# modulo_promini.net
KiCad netlist of a schematic drawn in EAGLE
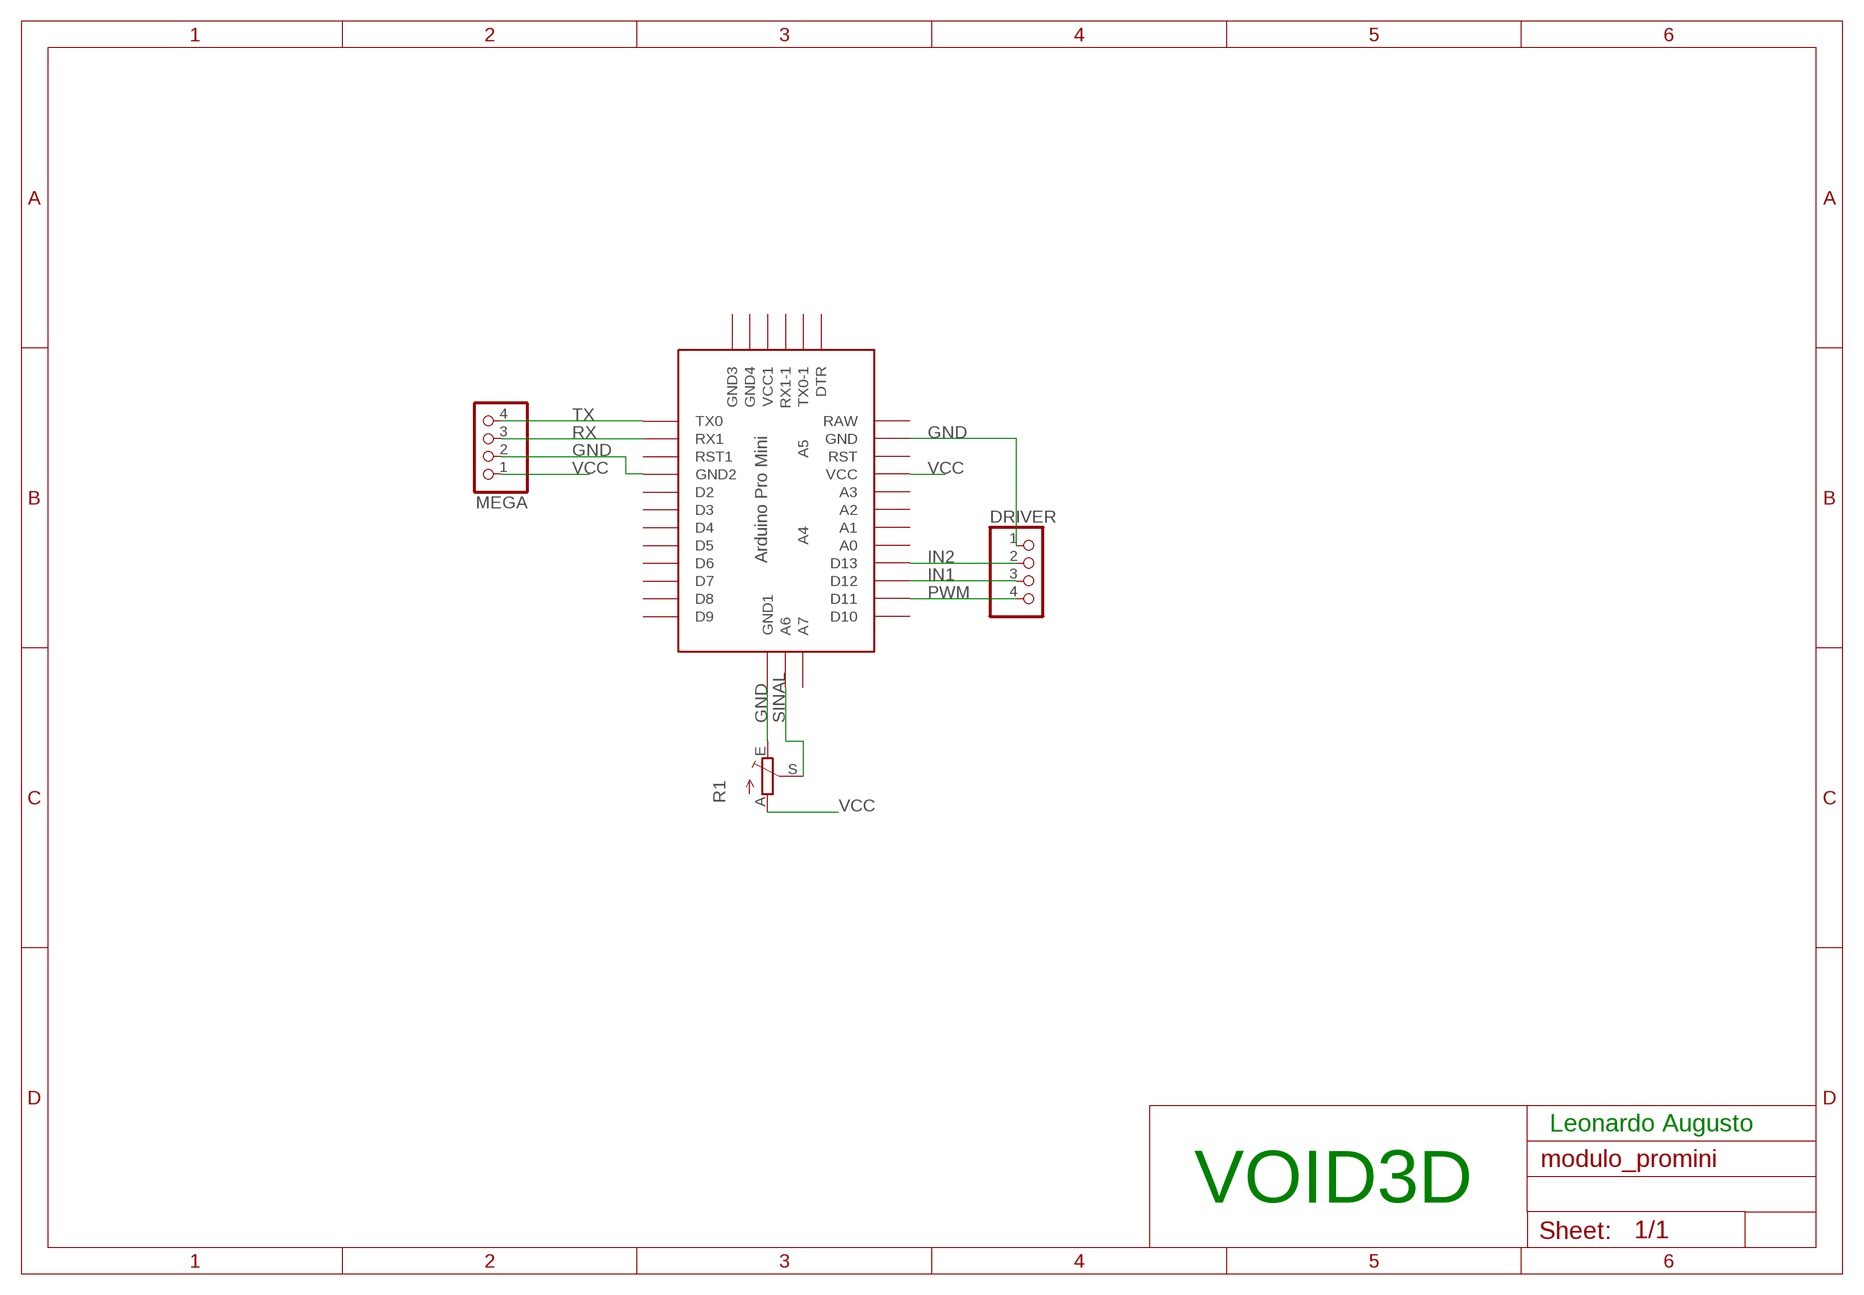
[diagram p0: schematic, sheet 1]

(export (version "E")
  (design (tool "Eeschema 10.0.6"))
  (components
    (comp (ref "DRIVER")
      (value "PINHD-1X4")
      (footprint "eagle-import:1X04")
      (libsource (lib "eagle-import") (part "PINHD-1X4"))
    )
    (comp (ref "MEGA")
      (value "PINHD-1X4")
      (footprint "eagle-import:1X04")
      (libsource (lib "eagle-import") (part "PINHD-1X4"))
    )
    (comp (ref "R1")
      (value "TRIM_EU-CA9V")
      (footprint "eagle-import:CA9V")
      (libsource (lib "eagle-import") (part "TRIM_EU-CA9V"))
    )
    (comp (ref "U$1")
      (value "ABK-PRO-MINI")
      (footprint "eagle-import:ABK-PRO-MINI")
      (libsource (lib "eagle-import") (part "ABK-PRO-MINI"))
    )
  )
  (nets
    (net (code "1") (name "/GND") (class "Default")
      (node (ref "DRIVER") (pin "1") (pinfunction "1_1") (pintype "passive"))
      (node (ref "MEGA") (pin "2") (pinfunction "2_2") (pintype "passive"))
      (node (ref "R1") (pin "E") (pinfunction "E_E") (pintype "passive"))
      (node (ref "U$1") (pin "GND") (pinfunction "GND_GND") (pintype "bidirectional"))
      (node (ref "U$1") (pin "GND1") (pinfunction "GND2_GND1") (pintype "bidirectional"))
      (node (ref "U$1") (pin "GND4") (pinfunction "GND1_GND4") (pintype "bidirectional"))
    )
    (net (code "2") (name "/IN1") (class "Default")
      (node (ref "DRIVER") (pin "3") (pinfunction "3_3") (pintype "passive"))
      (node (ref "U$1") (pin "D12") (pinfunction "D12_D12") (pintype "bidirectional"))
    )
    (net (code "3") (name "/IN2") (class "Default")
      (node (ref "DRIVER") (pin "2") (pinfunction "2_2") (pintype "passive"))
      (node (ref "U$1") (pin "D13") (pinfunction "D13_D13") (pintype "bidirectional"))
    )
    (net (code "4") (name "/PWM") (class "Default")
      (node (ref "DRIVER") (pin "4") (pinfunction "4_4") (pintype "passive"))
      (node (ref "U$1") (pin "D11") (pinfunction "D11_D11") (pintype "bidirectional"))
    )
    (net (code "5") (name "/RX") (class "Default")
      (node (ref "MEGA") (pin "3") (pinfunction "3_3") (pintype "passive"))
      (node (ref "U$1") (pin "RX1") (pinfunction "RX1_RX1") (pintype "bidirectional"))
    )
    (net (code "6") (name "/SINAL") (class "Default")
      (node (ref "R1") (pin "S") (pinfunction "S_S") (pintype "passive"))
      (node (ref "U$1") (pin "A6") (pinfunction "A6_A6") (pintype "bidirectional"))
    )
    (net (code "7") (name "/TX") (class "Default")
      (node (ref "MEGA") (pin "4") (pinfunction "4_4") (pintype "passive"))
      (node (ref "U$1") (pin "TX0") (pinfunction "TX0_TX0") (pintype "bidirectional"))
    )
    (net (code "8") (name "/VCC") (class "Default")
      (node (ref "MEGA") (pin "1") (pinfunction "1_1") (pintype "passive"))
      (node (ref "R1") (pin "A") (pinfunction "A_A") (pintype "passive"))
      (node (ref "U$1") (pin "VCC") (pinfunction "VCC_VCC") (pintype "bidirectional"))
    )
    (net (code "9") (name "unconnected-(U$1-GND3-PadGND2)") (class "Default")
      (node (ref "U$1") (pin "GND2") (pinfunction "GND3_GND2") (pintype "bidirectional"))
    )
    (net (code "10") (name "unconnected-(U$1-GND4-PadGND3)") (class "Default")
      (node (ref "U$1") (pin "GND3") (pinfunction "GND4_GND3") (pintype "bidirectional"))
    )
    (net (code "11") (name "unconnected-(U$1-PadA0)") (class "Default")
      (node (ref "U$1") (pin "A0") (pinfunction "A0_A0") (pintype "bidirectional"))
    )
    (net (code "12") (name "unconnected-(U$1-PadA1)") (class "Default")
      (node (ref "U$1") (pin "A1") (pinfunction "A1_A1") (pintype "bidirectional"))
    )
    (net (code "13") (name "unconnected-(U$1-PadA2)") (class "Default")
      (node (ref "U$1") (pin "A2") (pinfunction "A2_A2") (pintype "bidirectional"))
    )
    (net (code "14") (name "unconnected-(U$1-PadA3)") (class "Default")
      (node (ref "U$1") (pin "A3") (pinfunction "A3_A3") (pintype "bidirectional"))
    )
    (net (code "15") (name "unconnected-(U$1-PadA4)") (class "Default")
      (node (ref "U$1") (pin "A4") (pinfunction "A4_A4") (pintype "bidirectional"))
    )
    (net (code "16") (name "unconnected-(U$1-PadA5)") (class "Default")
      (node (ref "U$1") (pin "A5") (pinfunction "A5_A5") (pintype "bidirectional"))
    )
    (net (code "17") (name "unconnected-(U$1-PadA7)") (class "Default")
      (node (ref "U$1") (pin "A7") (pinfunction "A7_A7") (pintype "bidirectional"))
    )
    (net (code "18") (name "unconnected-(U$1-PadD2)") (class "Default")
      (node (ref "U$1") (pin "D2") (pinfunction "D2_D2") (pintype "bidirectional"))
    )
    (net (code "19") (name "unconnected-(U$1-PadD3)") (class "Default")
      (node (ref "U$1") (pin "D3") (pinfunction "D3_D3") (pintype "bidirectional"))
    )
    (net (code "20") (name "unconnected-(U$1-PadD4)") (class "Default")
      (node (ref "U$1") (pin "D4") (pinfunction "D4_D4") (pintype "bidirectional"))
    )
    (net (code "21") (name "unconnected-(U$1-PadD5)") (class "Default")
      (node (ref "U$1") (pin "D5") (pinfunction "D5_D5") (pintype "bidirectional"))
    )
    (net (code "22") (name "unconnected-(U$1-PadD6)") (class "Default")
      (node (ref "U$1") (pin "D6") (pinfunction "D6_D6") (pintype "bidirectional"))
    )
    (net (code "23") (name "unconnected-(U$1-PadD7)") (class "Default")
      (node (ref "U$1") (pin "D7") (pinfunction "D7_D7") (pintype "bidirectional"))
    )
    (net (code "24") (name "unconnected-(U$1-PadD8)") (class "Default")
      (node (ref "U$1") (pin "D8") (pinfunction "D8_D8") (pintype "bidirectional"))
    )
    (net (code "25") (name "unconnected-(U$1-PadD9)") (class "Default")
      (node (ref "U$1") (pin "D9") (pinfunction "D9_D9") (pintype "bidirectional"))
    )
    (net (code "26") (name "unconnected-(U$1-PadD10)") (class "Default")
      (node (ref "U$1") (pin "D10") (pinfunction "D10_D10") (pintype "bidirectional"))
    )
    (net (code "27") (name "unconnected-(U$1-PadDTR)") (class "Default")
      (node (ref "U$1") (pin "DTR") (pinfunction "DTR_DTR") (pintype "bidirectional"))
    )
    (net (code "28") (name "unconnected-(U$1-PadRAW)") (class "Default")
      (node (ref "U$1") (pin "RAW") (pinfunction "RAW_RAW") (pintype "bidirectional"))
    )
    (net (code "29") (name "unconnected-(U$1-PadRST)") (class "Default")
      (node (ref "U$1") (pin "RST") (pinfunction "RST_RST") (pintype "bidirectional"))
    )
    (net (code "30") (name "unconnected-(U$1-PadRST1)") (class "Default")
      (node (ref "U$1") (pin "RST1") (pinfunction "RST1_RST1") (pintype "bidirectional"))
    )
    (net (code "31") (name "unconnected-(U$1-PadRX1-1)") (class "Default")
      (node (ref "U$1") (pin "RX1-1") (pinfunction "RX1-1_RX1-1") (pintype "bidirectional"))
    )
    (net (code "32") (name "unconnected-(U$1-PadTX0-1)") (class "Default")
      (node (ref "U$1") (pin "TX0-1") (pinfunction "TX0-1_TX0-1") (pintype "bidirectional"))
    )
    (net (code "33") (name "unconnected-(U$1-PadVCC1)") (class "Default")
      (node (ref "U$1") (pin "VCC1") (pinfunction "VCC1_VCC1") (pintype "bidirectional"))
    )
  )
)
